# Arduino_MEGA_blank_shield.net
KiCad netlist of a schematic drawn in Altium Designer
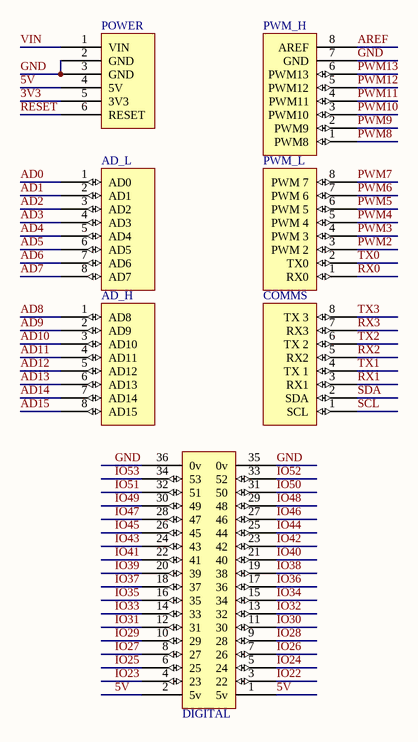
[diagram p0: Arduino MEGA blank shield.SchDoc]

(export (version "E")
  (design (tool "Eeschema 10.0.6"))
  (components
    (comp (ref "AD_H") (value "AD_H") (footprint "Header 8x1 8.5mm") (libsource (lib "Header") (part "AD_H")))
    (comp (ref "AD_L") (value "AD_L") (footprint "Header 8x1 8.5mm") (libsource (lib "Header") (part "AD_L")))
    (comp (ref "COMMS")
      (value "Communication")
      (footprint "Header 8x1 8.5mm")
      (libsource (lib "Header") (part "Communication"))
    )
    (comp (ref "DIGITAL")
      (value "IO_36")
      (footprint "HEADER 36X 8MM")
      (libsource (lib "Header") (part "IO_36"))
    )
    (comp (ref "POWER")
      (value "POWER")
      (footprint "Header 6x1 8.5mm")
      (libsource (lib "Header") (part "POWER"))
    )
    (comp (ref "PWM_H")
      (value "PWM_H")
      (footprint "Header 8x1 8.5mm")
      (libsource (lib "Header") (part "PWM_H"))
    )
    (comp (ref "PWM_L")
      (value "PWM_L")
      (footprint "Header 8x1 8.5mm")
      (libsource (lib "Header") (part "PWM_L"))
    )
  )
  (nets
    (net (code "1") (name "/3V3") (class "Default")
      (node (ref "POWER") (pin "5") (pinfunction "3V3_5") (pintype "power_in"))
    )
    (net (code "2") (name "/5V") (class "Default")
      (node (ref "DIGITAL") (pin "1") (pinfunction "5v_1") (pintype "power_in"))
      (node (ref "DIGITAL") (pin "2") (pinfunction "5v_2") (pintype "power_in"))
      (node (ref "POWER") (pin "4") (pinfunction "5V_4") (pintype "power_in"))
    )
    (net (code "3") (name "/AD0") (class "Default")
      (node (ref "AD_L") (pin "1") (pinfunction "AD0_1") (pintype "bidirectional"))
    )
    (net (code "4") (name "/AD1") (class "Default")
      (node (ref "AD_L") (pin "2") (pinfunction "AD1_2") (pintype "bidirectional"))
    )
    (net (code "5") (name "/AD2") (class "Default")
      (node (ref "AD_L") (pin "3") (pinfunction "AD2_3") (pintype "bidirectional"))
    )
    (net (code "6") (name "/AD3") (class "Default")
      (node (ref "AD_L") (pin "4") (pinfunction "AD3_4") (pintype "bidirectional"))
    )
    (net (code "7") (name "/AD4") (class "Default")
      (node (ref "AD_L") (pin "5") (pinfunction "AD4_5") (pintype "bidirectional"))
    )
    (net (code "8") (name "/AD5") (class "Default")
      (node (ref "AD_L") (pin "6") (pinfunction "AD5_6") (pintype "bidirectional"))
    )
    (net (code "9") (name "/AD6") (class "Default")
      (node (ref "AD_L") (pin "7") (pinfunction "AD6_7") (pintype "bidirectional"))
    )
    (net (code "10") (name "/AD7") (class "Default")
      (node (ref "AD_L") (pin "8") (pinfunction "AD7_8") (pintype "bidirectional"))
    )
    (net (code "11") (name "/AD8") (class "Default")
      (node (ref "AD_H") (pin "1") (pinfunction "AD8_1") (pintype "bidirectional"))
    )
    (net (code "12") (name "/AD9") (class "Default")
      (node (ref "AD_H") (pin "2") (pinfunction "AD9_2") (pintype "bidirectional"))
    )
    (net (code "13") (name "/AD10") (class "Default")
      (node (ref "AD_H") (pin "3") (pinfunction "AD10_3") (pintype "bidirectional"))
    )
    (net (code "14") (name "/AD11") (class "Default")
      (node (ref "AD_H") (pin "4") (pinfunction "AD11_4") (pintype "bidirectional"))
    )
    (net (code "15") (name "/AD12") (class "Default")
      (node (ref "AD_H") (pin "5") (pinfunction "AD12_5") (pintype "bidirectional"))
    )
    (net (code "16") (name "/AD13") (class "Default")
      (node (ref "AD_H") (pin "6") (pinfunction "AD13_6") (pintype "bidirectional"))
    )
    (net (code "17") (name "/AD14") (class "Default")
      (node (ref "AD_H") (pin "7") (pinfunction "AD14_7") (pintype "bidirectional"))
    )
    (net (code "18") (name "/AD15") (class "Default")
      (node (ref "AD_H") (pin "8") (pinfunction "AD15_8") (pintype "bidirectional"))
    )
    (net (code "19") (name "/AREF") (class "Default")
      (node (ref "PWM_H") (pin "8") (pinfunction "AREF_8") (pintype "passive"))
    )
    (net (code "20") (name "/GND") (class "Default")
      (node (ref "DIGITAL") (pin "35") (pinfunction "0v_35") (pintype "power_in"))
      (node (ref "DIGITAL") (pin "36") (pinfunction "0v_36") (pintype "power_in"))
      (node (ref "POWER") (pin "2") (pinfunction "GND_2") (pintype "power_in"))
      (node (ref "POWER") (pin "3") (pinfunction "GND_3") (pintype "power_in"))
      (node (ref "PWM_H") (pin "7") (pinfunction "GND_7") (pintype "power_in"))
    )
    (net (code "21") (name "/IO22") (class "Default")
      (node (ref "DIGITAL") (pin "3") (pinfunction "22_3") (pintype "bidirectional"))
    )
    (net (code "22") (name "/IO23") (class "Default")
      (node (ref "DIGITAL") (pin "4") (pinfunction "23_4") (pintype "bidirectional"))
    )
    (net (code "23") (name "/IO24") (class "Default")
      (node (ref "DIGITAL") (pin "5") (pinfunction "24_5") (pintype "bidirectional"))
    )
    (net (code "24") (name "/IO25") (class "Default")
      (node (ref "DIGITAL") (pin "6") (pinfunction "25_6") (pintype "bidirectional"))
    )
    (net (code "25") (name "/IO26") (class "Default")
      (node (ref "DIGITAL") (pin "7") (pinfunction "26_7") (pintype "bidirectional"))
    )
    (net (code "26") (name "/IO27") (class "Default")
      (node (ref "DIGITAL") (pin "8") (pinfunction "27_8") (pintype "bidirectional"))
    )
    (net (code "27") (name "/IO28") (class "Default")
      (node (ref "DIGITAL") (pin "9") (pinfunction "28_9") (pintype "bidirectional"))
    )
    (net (code "28") (name "/IO29") (class "Default")
      (node (ref "DIGITAL") (pin "10") (pinfunction "29_10") (pintype "bidirectional"))
    )
    (net (code "29") (name "/IO30") (class "Default")
      (node (ref "DIGITAL") (pin "11") (pinfunction "30_11") (pintype "bidirectional"))
    )
    (net (code "30") (name "/IO31") (class "Default")
      (node (ref "DIGITAL") (pin "12") (pinfunction "31_12") (pintype "bidirectional"))
    )
    (net (code "31") (name "/IO32") (class "Default")
      (node (ref "DIGITAL") (pin "13") (pinfunction "32_13") (pintype "bidirectional"))
    )
    (net (code "32") (name "/IO33") (class "Default")
      (node (ref "DIGITAL") (pin "14") (pinfunction "33_14") (pintype "bidirectional"))
    )
    (net (code "33") (name "/IO34") (class "Default")
      (node (ref "DIGITAL") (pin "15") (pinfunction "34_15") (pintype "bidirectional"))
    )
    (net (code "34") (name "/IO35") (class "Default")
      (node (ref "DIGITAL") (pin "16") (pinfunction "35_16") (pintype "bidirectional"))
    )
    (net (code "35") (name "/IO36") (class "Default")
      (node (ref "DIGITAL") (pin "17") (pinfunction "36_17") (pintype "bidirectional"))
    )
    (net (code "36") (name "/IO37") (class "Default")
      (node (ref "DIGITAL") (pin "18") (pinfunction "37_18") (pintype "bidirectional"))
    )
    (net (code "37") (name "/IO38") (class "Default")
      (node (ref "DIGITAL") (pin "19") (pinfunction "38_19") (pintype "bidirectional"))
    )
    (net (code "38") (name "/IO39") (class "Default")
      (node (ref "DIGITAL") (pin "20") (pinfunction "39_20") (pintype "bidirectional"))
    )
    (net (code "39") (name "/IO40") (class "Default")
      (node (ref "DIGITAL") (pin "21") (pinfunction "40_21") (pintype "bidirectional"))
    )
    (net (code "40") (name "/IO41") (class "Default")
      (node (ref "DIGITAL") (pin "22") (pinfunction "41_22") (pintype "bidirectional"))
    )
    (net (code "41") (name "/IO42") (class "Default")
      (node (ref "DIGITAL") (pin "23") (pinfunction "42_23") (pintype "bidirectional"))
    )
    (net (code "42") (name "/IO43") (class "Default")
      (node (ref "DIGITAL") (pin "24") (pinfunction "43_24") (pintype "bidirectional"))
    )
    (net (code "43") (name "/IO44") (class "Default")
      (node (ref "DIGITAL") (pin "25") (pinfunction "44_25") (pintype "bidirectional"))
    )
    (net (code "44") (name "/IO45") (class "Default")
      (node (ref "DIGITAL") (pin "26") (pinfunction "45_26") (pintype "bidirectional"))
    )
    (net (code "45") (name "/IO46") (class "Default")
      (node (ref "DIGITAL") (pin "27") (pinfunction "46_27") (pintype "bidirectional"))
    )
    (net (code "46") (name "/IO47") (class "Default")
      (node (ref "DIGITAL") (pin "28") (pinfunction "47_28") (pintype "bidirectional"))
    )
    (net (code "47") (name "/IO48") (class "Default")
      (node (ref "DIGITAL") (pin "29") (pinfunction "48_29") (pintype "bidirectional"))
    )
    (net (code "48") (name "/IO49") (class "Default")
      (node (ref "DIGITAL") (pin "30") (pinfunction "49_30") (pintype "bidirectional"))
    )
    (net (code "49") (name "/IO50") (class "Default")
      (node (ref "DIGITAL") (pin "31") (pinfunction "50_31") (pintype "bidirectional"))
    )
    (net (code "50") (name "/IO51") (class "Default")
      (node (ref "DIGITAL") (pin "32") (pinfunction "51_32") (pintype "bidirectional"))
    )
    (net (code "51") (name "/IO52") (class "Default")
      (node (ref "DIGITAL") (pin "33") (pinfunction "52_33") (pintype "bidirectional"))
    )
    (net (code "52") (name "/IO53") (class "Default")
      (node (ref "DIGITAL") (pin "34") (pinfunction "53_34") (pintype "bidirectional"))
    )
    (net (code "53") (name "/PWM2") (class "Default")
      (node (ref "PWM_L") (pin "3") (pinfunction "PWM_2_3") (pintype "bidirectional"))
    )
    (net (code "54") (name "/PWM3") (class "Default")
      (node (ref "PWM_L") (pin "4") (pinfunction "PWM_3_4") (pintype "bidirectional"))
    )
    (net (code "55") (name "/PWM4") (class "Default")
      (node (ref "PWM_L") (pin "5") (pinfunction "PWM_4_5") (pintype "bidirectional"))
    )
    (net (code "56") (name "/PWM5") (class "Default")
      (node (ref "PWM_L") (pin "6") (pinfunction "PWM_5_6") (pintype "bidirectional"))
    )
    (net (code "57") (name "/PWM6") (class "Default")
      (node (ref "PWM_L") (pin "7") (pinfunction "PWM_6_7") (pintype "bidirectional"))
    )
    (net (code "58") (name "/PWM7") (class "Default")
      (node (ref "PWM_L") (pin "8") (pinfunction "PWM_7_8") (pintype "bidirectional"))
    )
    (net (code "59") (name "/PWM8") (class "Default")
      (node (ref "PWM_H") (pin "1") (pinfunction "PWM8_1") (pintype "bidirectional"))
    )
    (net (code "60") (name "/PWM9") (class "Default")
      (node (ref "PWM_H") (pin "2") (pinfunction "PWM9_2") (pintype "bidirectional"))
    )
    (net (code "61") (name "/PWM10") (class "Default")
      (node (ref "PWM_H") (pin "3") (pinfunction "PWM10_3") (pintype "bidirectional"))
    )
    (net (code "62") (name "/PWM11") (class "Default")
      (node (ref "PWM_H") (pin "4") (pinfunction "PWM11_4") (pintype "bidirectional"))
    )
    (net (code "63") (name "/PWM12") (class "Default")
      (node (ref "PWM_H") (pin "5") (pinfunction "PWM12_5") (pintype "bidirectional"))
    )
    (net (code "64") (name "/PWM13") (class "Default")
      (node (ref "PWM_H") (pin "6") (pinfunction "PWM13_6") (pintype "bidirectional"))
    )
    (net (code "65") (name "/RESET") (class "Default")
      (node (ref "POWER") (pin "6") (pinfunction "RESET_6") (pintype "passive"))
    )
    (net (code "66") (name "/RX0") (class "Default")
      (node (ref "PWM_L") (pin "1") (pinfunction "RX0_1") (pintype "bidirectional"))
    )
    (net (code "67") (name "/RX1") (class "Default")
      (node (ref "COMMS") (pin "3") (pinfunction "RX1_3") (pintype "bidirectional"))
    )
    (net (code "68") (name "/RX2") (class "Default")
      (node (ref "COMMS") (pin "5") (pinfunction "RX2_5") (pintype "bidirectional"))
    )
    (net (code "69") (name "/RX3") (class "Default")
      (node (ref "COMMS") (pin "7") (pinfunction "RX3_7") (pintype "bidirectional"))
    )
    (net (code "70") (name "/SCL") (class "Default")
      (node (ref "COMMS") (pin "1") (pinfunction "SCL_1") (pintype "bidirectional"))
    )
    (net (code "71") (name "/SDA") (class "Default")
      (node (ref "COMMS") (pin "2") (pinfunction "SDA_2") (pintype "bidirectional"))
    )
    (net (code "72") (name "/TX0") (class "Default")
      (node (ref "PWM_L") (pin "2") (pinfunction "TX0_2") (pintype "bidirectional"))
    )
    (net (code "73") (name "/TX1") (class "Default")
      (node (ref "COMMS") (pin "4") (pinfunction "TX_1_4") (pintype "bidirectional"))
    )
    (net (code "74") (name "/TX2") (class "Default")
      (node (ref "COMMS") (pin "6") (pinfunction "TX_2_6") (pintype "bidirectional"))
    )
    (net (code "75") (name "/TX3") (class "Default")
      (node (ref "COMMS") (pin "8") (pinfunction "TX_3_8") (pintype "bidirectional"))
    )
    (net (code "76") (name "/VIN") (class "Default")
      (node (ref "POWER") (pin "1") (pinfunction "VIN_1") (pintype "power_in"))
    )
  )
)
